# latch4.net
KiCad netlist of a schematic drawn in EAGLE
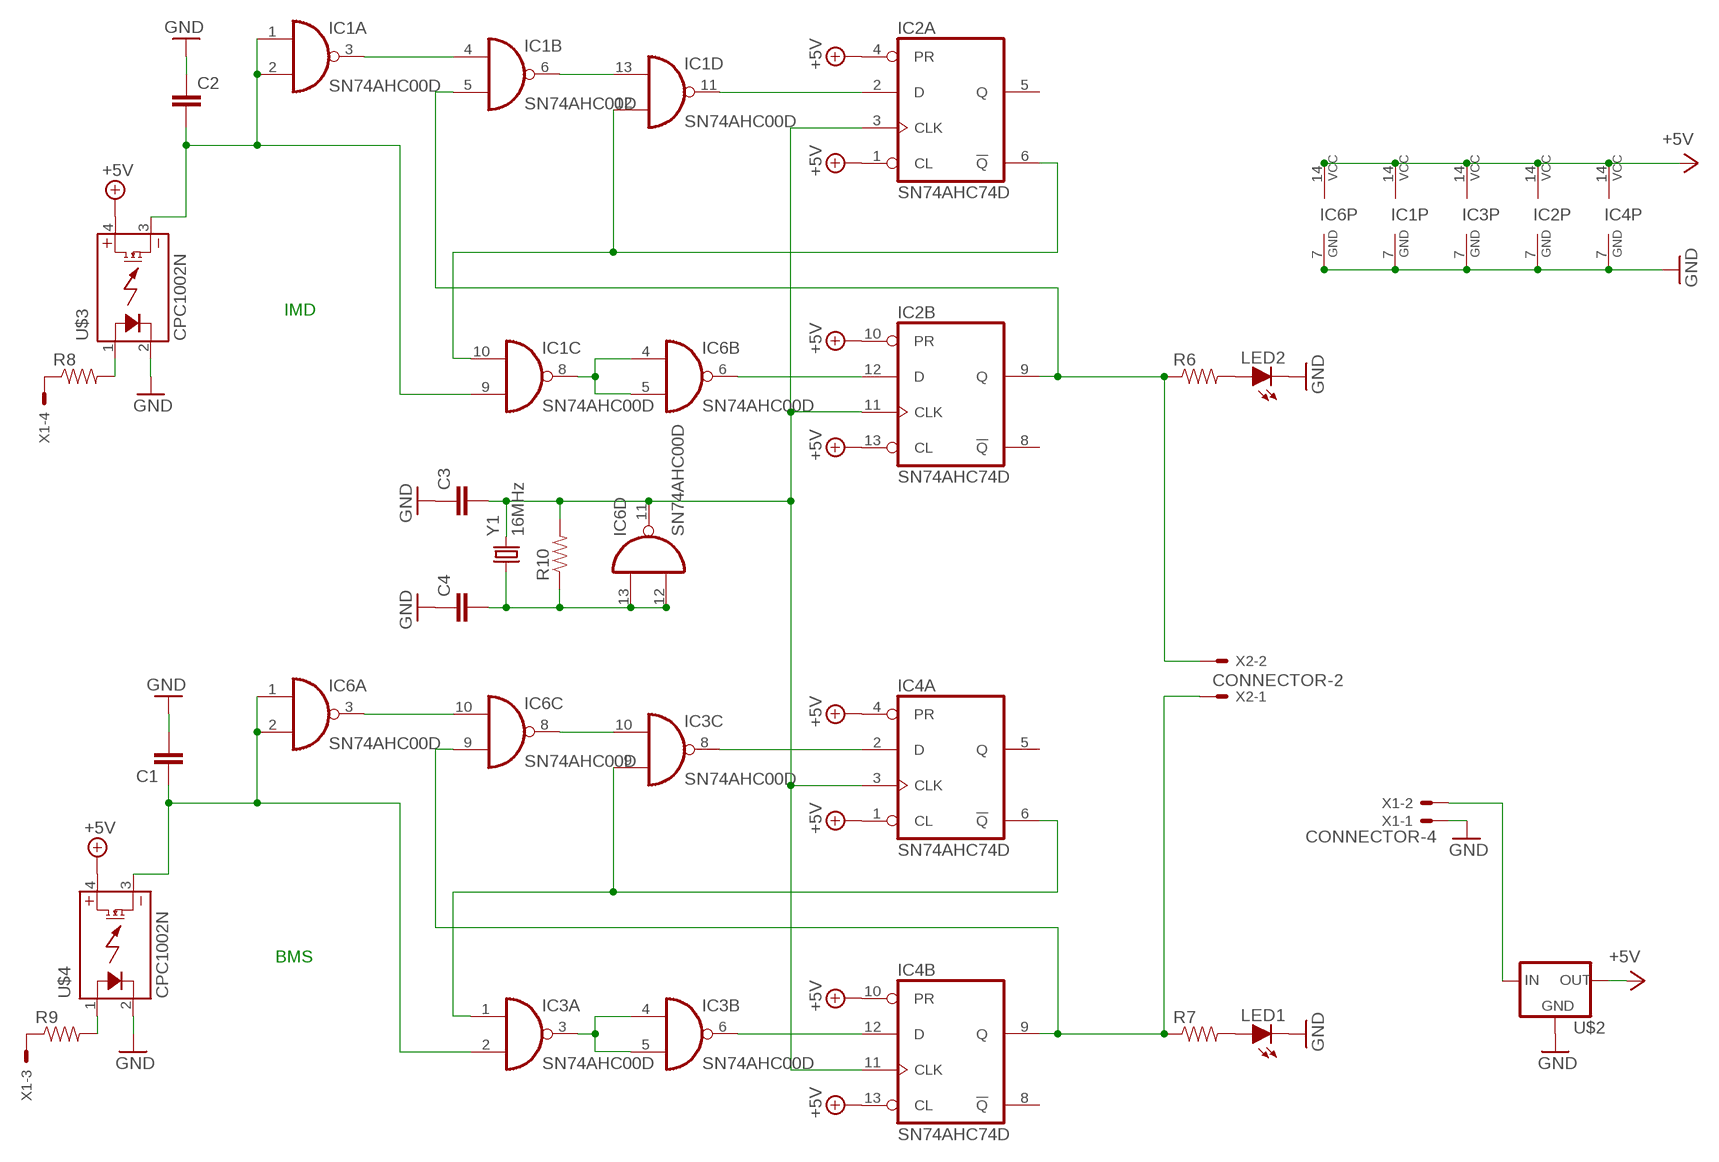
[diagram p0: schematic, sheet 1]

(export (version "E")
  (design (tool "Eeschema 10.0.6"))
  (components
    (comp (ref "C1")
      (value "CAP0402-CAP")
      (footprint "eagle-import:0402-CAP")
      (libsource (lib "eagle-import") (part "CAP0402-CAP"))
    )
    (comp (ref "C2")
      (value "CAP0402-CAP")
      (footprint "eagle-import:0402-CAP")
      (libsource (lib "eagle-import") (part "CAP0402-CAP"))
    )
    (comp (ref "C3")
      (value "CAP0402-CAP")
      (footprint "eagle-import:0402-CAP")
      (libsource (lib "eagle-import") (part "CAP0402-CAP"))
    )
    (comp (ref "C4")
      (value "CAP0402-CAP")
      (footprint "eagle-import:0402-CAP")
      (libsource (lib "eagle-import") (part "CAP0402-CAP"))
    )
    (comp (ref "IC1")
      (value "SN74AHC00D")
      (footprint "eagle-import:SOIC-14")
      (libsource (lib "eagle-import") (part "SN74AHC00D"))
    )
    (comp (ref "IC2")
      (value "SN74AHC74D")
      (footprint "eagle-import:SOIC-14")
      (libsource (lib "eagle-import") (part "SN74AHC74D"))
    )
    (comp (ref "IC3")
      (value "SN74AHC00D")
      (footprint "eagle-import:SOIC-14")
      (libsource (lib "eagle-import") (part "SN74AHC00D"))
    )
    (comp (ref "IC4")
      (value "SN74AHC74D")
      (footprint "eagle-import:SOIC-14")
      (libsource (lib "eagle-import") (part "SN74AHC74D"))
    )
    (comp (ref "IC6")
      (value "SN74AHC00D")
      (footprint "eagle-import:SOIC-14")
      (libsource (lib "eagle-import") (part "SN74AHC00D"))
    )
    (comp (ref "LED1")
      (value "LED-0805")
      (footprint "eagle-import:LED-805")
      (libsource (lib "eagle-import") (part "LED-0805"))
    )
    (comp (ref "LED2")
      (value "LED-0805")
      (footprint "eagle-import:LED-805")
      (libsource (lib "eagle-import") (part "LED-0805"))
    )
    (comp (ref "R6")
      (value "RESISTOR0402")
      (footprint "eagle-import:0402-RES")
      (libsource (lib "eagle-import") (part "RESISTOR0402"))
    )
    (comp (ref "R7")
      (value "RESISTOR0402")
      (footprint "eagle-import:0402-RES")
      (libsource (lib "eagle-import") (part "RESISTOR0402"))
    )
    (comp (ref "R8")
      (value "RESISTOR0402")
      (footprint "eagle-import:0402-RES")
      (libsource (lib "eagle-import") (part "RESISTOR0402"))
    )
    (comp (ref "R9")
      (value "RESISTOR0402")
      (footprint "eagle-import:0402-RES")
      (libsource (lib "eagle-import") (part "RESISTOR0402"))
    )
    (comp (ref "R10")
      (value "RESISTOR0402")
      (footprint "eagle-import:0402-RES")
      (libsource (lib "eagle-import") (part "RESISTOR0402"))
    )
    (comp (ref "U$2")
      (value "5VREG_LM340-NLM340MPX-5.0/NOPB")
      (footprint "eagle-import:SOT223")
      (libsource (lib "eagle-import") (part "5VREG_LM340-NLM340MPX-5.0/NOPB"))
    )
    (comp (ref "U$3")
      (value "CPC1002N")
      (footprint "eagle-import:SOP04")
      (libsource (lib "eagle-import") (part "CPC1002N"))
    )
    (comp (ref "U$4")
      (value "CPC1002N")
      (footprint "eagle-import:SOP04")
      (libsource (lib "eagle-import") (part "CPC1002N"))
    )
    (comp (ref "X1")
      (value "CONNECTOR-4")
      (footprint "eagle-import:MINIFIT_5566-4")
      (libsource (lib "eagle-import") (part "CONNECTOR-4"))
    )
    (comp (ref "X2")
      (value "CONNECTOR-2")
      (footprint "eagle-import:MINIFIT_5566-2")
      (libsource (lib "eagle-import") (part "CONNECTOR-2"))
    )
    (comp (ref "Y1")
      (value "16MHz")
      (footprint "eagle-import:CRYSTAL-SMD-3.2X1.5MM")
      (libsource (lib "eagle-import") (part "CRYSTAL3.2X1.5MM"))
    )
  )
  (nets
    (net (code "1") (name "+5V") (class "Default")
      (node (ref "IC1") (pin "14") (pinfunction "VCC_14") (pintype "power_in"))
      (node (ref "IC2") (pin "1") (pinfunction "CL_1") (pintype "input"))
      (node (ref "IC2") (pin "10") (pinfunction "PR_10") (pintype "input"))
      (node (ref "IC2") (pin "13") (pinfunction "CL_13") (pintype "input"))
      (node (ref "IC2") (pin "14") (pinfunction "VCC_14") (pintype "power_in"))
      (node (ref "IC2") (pin "4") (pinfunction "PR_4") (pintype "input"))
      (node (ref "IC3") (pin "14") (pinfunction "VCC_14") (pintype "power_in"))
      (node (ref "IC4") (pin "1") (pinfunction "CL_1") (pintype "input"))
      (node (ref "IC4") (pin "10") (pinfunction "PR_10") (pintype "input"))
      (node (ref "IC4") (pin "13") (pinfunction "CL_13") (pintype "input"))
      (node (ref "IC4") (pin "14") (pinfunction "VCC_14") (pintype "power_in"))
      (node (ref "IC4") (pin "4") (pinfunction "PR_4") (pintype "input"))
      (node (ref "IC6") (pin "14") (pinfunction "VCC_14") (pintype "power_in"))
      (node (ref "U$2") (pin "3") (pinfunction "OUT_3") (pintype "output"))
      (node (ref "U$3") (pin "4") (pinfunction "DC+_4") (pintype "passive"))
      (node (ref "U$4") (pin "4") (pinfunction "DC+_4") (pintype "passive"))
    )
    (net (code "2") (name "GND") (class "Default")
      (node (ref "C1") (pin "2") (pinfunction "2_2") (pintype "passive"))
      (node (ref "C2") (pin "1") (pinfunction "1_1") (pintype "passive"))
      (node (ref "C3") (pin "1") (pinfunction "1_1") (pintype "passive"))
      (node (ref "C4") (pin "1") (pinfunction "1_1") (pintype "passive"))
      (node (ref "IC1") (pin "7") (pinfunction "GND_7") (pintype "power_in"))
      (node (ref "IC2") (pin "7") (pinfunction "GND_7") (pintype "power_in"))
      (node (ref "IC3") (pin "7") (pinfunction "GND_7") (pintype "power_in"))
      (node (ref "IC4") (pin "7") (pinfunction "GND_7") (pintype "power_in"))
      (node (ref "IC6") (pin "7") (pinfunction "GND_7") (pintype "power_in"))
      (node (ref "LED1") (pin "C") (pinfunction "C_C") (pintype "passive"))
      (node (ref "LED2") (pin "C") (pinfunction "C_C") (pintype "passive"))
      (node (ref "U$2") (pin "2") (pinfunction "GND_2") (pintype "input"))
      (node (ref "U$2") (pin "4") (pinfunction "GND_4") (pintype "input"))
      (node (ref "U$3") (pin "2") (pinfunction "CONTROL-_2") (pintype "passive"))
      (node (ref "U$4") (pin "2") (pinfunction "CONTROL-_2") (pintype "passive"))
      (node (ref "X1") (pin "1") (pinfunction "S_1") (pintype "passive"))
    )
    (net (code "3") (name "Net-(IC1A-I0)") (class "Default")
      (node (ref "C2") (pin "2") (pinfunction "2_2") (pintype "passive"))
      (node (ref "IC1") (pin "1") (pinfunction "I0_1") (pintype "input"))
      (node (ref "IC1") (pin "2") (pinfunction "I1_2") (pintype "input"))
      (node (ref "IC1") (pin "9") (pinfunction "I1_9") (pintype "input"))
      (node (ref "U$3") (pin "3") (pinfunction "DC-_3") (pintype "passive"))
    )
    (net (code "4") (name "Net-(IC1A-O)") (class "Default")
      (node (ref "IC1") (pin "3") (pinfunction "O_3") (pintype "output"))
      (node (ref "IC1") (pin "4") (pinfunction "I0_4") (pintype "input"))
    )
    (net (code "5") (name "Net-(IC1B-I1)") (class "Default")
      (node (ref "IC1") (pin "5") (pinfunction "I1_5") (pintype "input"))
      (node (ref "IC2") (pin "9") (pinfunction "Q_9") (pintype "output"))
      (node (ref "R6") (pin "1") (pinfunction "1_1") (pintype "passive"))
      (node (ref "X2") (pin "2") (pinfunction "S_2") (pintype "passive"))
    )
    (net (code "6") (name "Net-(IC1B-O)") (class "Default")
      (node (ref "IC1") (pin "13") (pinfunction "I0_13") (pintype "input"))
      (node (ref "IC1") (pin "6") (pinfunction "O_6") (pintype "output"))
    )
    (net (code "7") (name "Net-(IC1C-I0)") (class "Default")
      (node (ref "IC1") (pin "10") (pinfunction "I0_10") (pintype "input"))
      (node (ref "IC1") (pin "12") (pinfunction "I1_12") (pintype "input"))
      (node (ref "IC2") (pin "6") (pinfunction "~{Q}_6") (pintype "output"))
    )
    (net (code "8") (name "Net-(IC1C-O)") (class "Default")
      (node (ref "IC1") (pin "8") (pinfunction "O_8") (pintype "output"))
      (node (ref "IC6") (pin "4") (pinfunction "I0_4") (pintype "input"))
      (node (ref "IC6") (pin "5") (pinfunction "I1_5") (pintype "input"))
    )
    (net (code "9") (name "Net-(IC1D-O)") (class "Default")
      (node (ref "IC1") (pin "11") (pinfunction "O_11") (pintype "output"))
      (node (ref "IC2") (pin "2") (pinfunction "D_2") (pintype "input"))
    )
    (net (code "10") (name "Net-(IC2A-CLK)") (class "Default")
      (node (ref "C3") (pin "2") (pinfunction "2_2") (pintype "passive"))
      (node (ref "IC2") (pin "11") (pinfunction "CLK_11") (pintype "input"))
      (node (ref "IC2") (pin "3") (pinfunction "CLK_3") (pintype "input"))
      (node (ref "IC4") (pin "11") (pinfunction "CLK_11") (pintype "input"))
      (node (ref "IC4") (pin "3") (pinfunction "CLK_3") (pintype "input"))
      (node (ref "IC6") (pin "11") (pinfunction "O_11") (pintype "output"))
      (node (ref "R10") (pin "2") (pinfunction "2_2") (pintype "passive"))
      (node (ref "Y1") (pin "P$2") (pinfunction "2_P$2") (pintype "passive"))
    )
    (net (code "11") (name "Net-(IC2B-D)") (class "Default")
      (node (ref "IC2") (pin "12") (pinfunction "D_12") (pintype "input"))
      (node (ref "IC6") (pin "6") (pinfunction "O_6") (pintype "output"))
    )
    (net (code "12") (name "Net-(IC3A-I0)") (class "Default")
      (node (ref "IC3") (pin "1") (pinfunction "I0_1") (pintype "input"))
      (node (ref "IC3") (pin "9") (pinfunction "I1_9") (pintype "input"))
      (node (ref "IC4") (pin "6") (pinfunction "~{Q}_6") (pintype "output"))
    )
    (net (code "13") (name "Net-(IC3A-I1)") (class "Default")
      (node (ref "C1") (pin "1") (pinfunction "1_1") (pintype "passive"))
      (node (ref "IC3") (pin "2") (pinfunction "I1_2") (pintype "input"))
      (node (ref "IC6") (pin "1") (pinfunction "I0_1") (pintype "input"))
      (node (ref "IC6") (pin "2") (pinfunction "I1_2") (pintype "input"))
      (node (ref "U$4") (pin "3") (pinfunction "DC-_3") (pintype "passive"))
    )
    (net (code "14") (name "Net-(IC3A-O)") (class "Default")
      (node (ref "IC3") (pin "3") (pinfunction "O_3") (pintype "output"))
      (node (ref "IC3") (pin "4") (pinfunction "I0_4") (pintype "input"))
      (node (ref "IC3") (pin "5") (pinfunction "I1_5") (pintype "input"))
    )
    (net (code "15") (name "Net-(IC3B-O)") (class "Default")
      (node (ref "IC3") (pin "6") (pinfunction "O_6") (pintype "output"))
      (node (ref "IC4") (pin "12") (pinfunction "D_12") (pintype "input"))
    )
    (net (code "16") (name "Net-(IC3C-I0)") (class "Default")
      (node (ref "IC3") (pin "10") (pinfunction "I0_10") (pintype "input"))
      (node (ref "IC6") (pin "8") (pinfunction "O_8") (pintype "output"))
    )
    (net (code "17") (name "Net-(IC3C-O)") (class "Default")
      (node (ref "IC3") (pin "8") (pinfunction "O_8") (pintype "output"))
      (node (ref "IC4") (pin "2") (pinfunction "D_2") (pintype "input"))
    )
    (net (code "18") (name "Net-(IC4B-Q)") (class "Default")
      (node (ref "IC4") (pin "9") (pinfunction "Q_9") (pintype "output"))
      (node (ref "IC6") (pin "9") (pinfunction "I1_9") (pintype "input"))
      (node (ref "R7") (pin "1") (pinfunction "1_1") (pintype "passive"))
      (node (ref "X2") (pin "1") (pinfunction "S_1") (pintype "passive"))
    )
    (net (code "19") (name "Net-(IC6A-O)") (class "Default")
      (node (ref "IC6") (pin "10") (pinfunction "I0_10") (pintype "input"))
      (node (ref "IC6") (pin "3") (pinfunction "O_3") (pintype "output"))
    )
    (net (code "20") (name "Net-(IC6D-I0)") (class "Default")
      (node (ref "C4") (pin "2") (pinfunction "2_2") (pintype "passive"))
      (node (ref "IC6") (pin "12") (pinfunction "I1_12") (pintype "input"))
      (node (ref "IC6") (pin "13") (pinfunction "I0_13") (pintype "input"))
      (node (ref "R10") (pin "1") (pinfunction "1_1") (pintype "passive"))
      (node (ref "Y1") (pin "P$1") (pinfunction "1_P$1") (pintype "passive"))
    )
    (net (code "21") (name "Net-(LED1-PadA)") (class "Default")
      (node (ref "LED1") (pin "A") (pinfunction "A_A") (pintype "passive"))
      (node (ref "R7") (pin "2") (pinfunction "2_2") (pintype "passive"))
    )
    (net (code "22") (name "Net-(LED2-PadA)") (class "Default")
      (node (ref "LED2") (pin "A") (pinfunction "A_A") (pintype "passive"))
      (node (ref "R6") (pin "2") (pinfunction "2_2") (pintype "passive"))
    )
    (net (code "23") (name "Net-(U$2-IN)") (class "Default")
      (node (ref "U$2") (pin "1") (pinfunction "IN_1") (pintype "input"))
      (node (ref "X1") (pin "2") (pinfunction "S_2") (pintype "passive"))
    )
    (net (code "24") (name "Net-(U$3-CONTROL+)") (class "Default")
      (node (ref "R8") (pin "2") (pinfunction "2_2") (pintype "passive"))
      (node (ref "U$3") (pin "1") (pinfunction "CONTROL+_1") (pintype "passive"))
    )
    (net (code "25") (name "Net-(U$4-CONTROL+)") (class "Default")
      (node (ref "R9") (pin "2") (pinfunction "2_2") (pintype "passive"))
      (node (ref "U$4") (pin "1") (pinfunction "CONTROL+_1") (pintype "passive"))
    )
    (net (code "26") (name "Net-(X1C-S)") (class "Default")
      (node (ref "R9") (pin "1") (pinfunction "1_1") (pintype "passive"))
      (node (ref "X1") (pin "3") (pinfunction "S_3") (pintype "passive"))
    )
    (net (code "27") (name "Net-(X1D-S)") (class "Default")
      (node (ref "R8") (pin "1") (pinfunction "1_1") (pintype "passive"))
      (node (ref "X1") (pin "4") (pinfunction "S_4") (pintype "passive"))
    )
    (net (code "28") (name "unconnected-(IC2A-Q-Pad5)") (class "Default")
      (node (ref "IC2") (pin "5") (pinfunction "Q_5") (pintype "output"))
    )
    (net (code "29") (name "unconnected-(IC2B-~{Q}-Pad8)") (class "Default")
      (node (ref "IC2") (pin "8") (pinfunction "~{Q}_8") (pintype "output"))
    )
    (net (code "30") (name "unconnected-(IC4A-Q-Pad5)") (class "Default")
      (node (ref "IC4") (pin "5") (pinfunction "Q_5") (pintype "output"))
    )
    (net (code "31") (name "unconnected-(IC4B-~{Q}-Pad8)") (class "Default")
      (node (ref "IC4") (pin "8") (pinfunction "~{Q}_8") (pintype "output"))
    )
  )
)
